# Adafruit_PCF8591.net
KiCad netlist of a schematic drawn in EAGLE
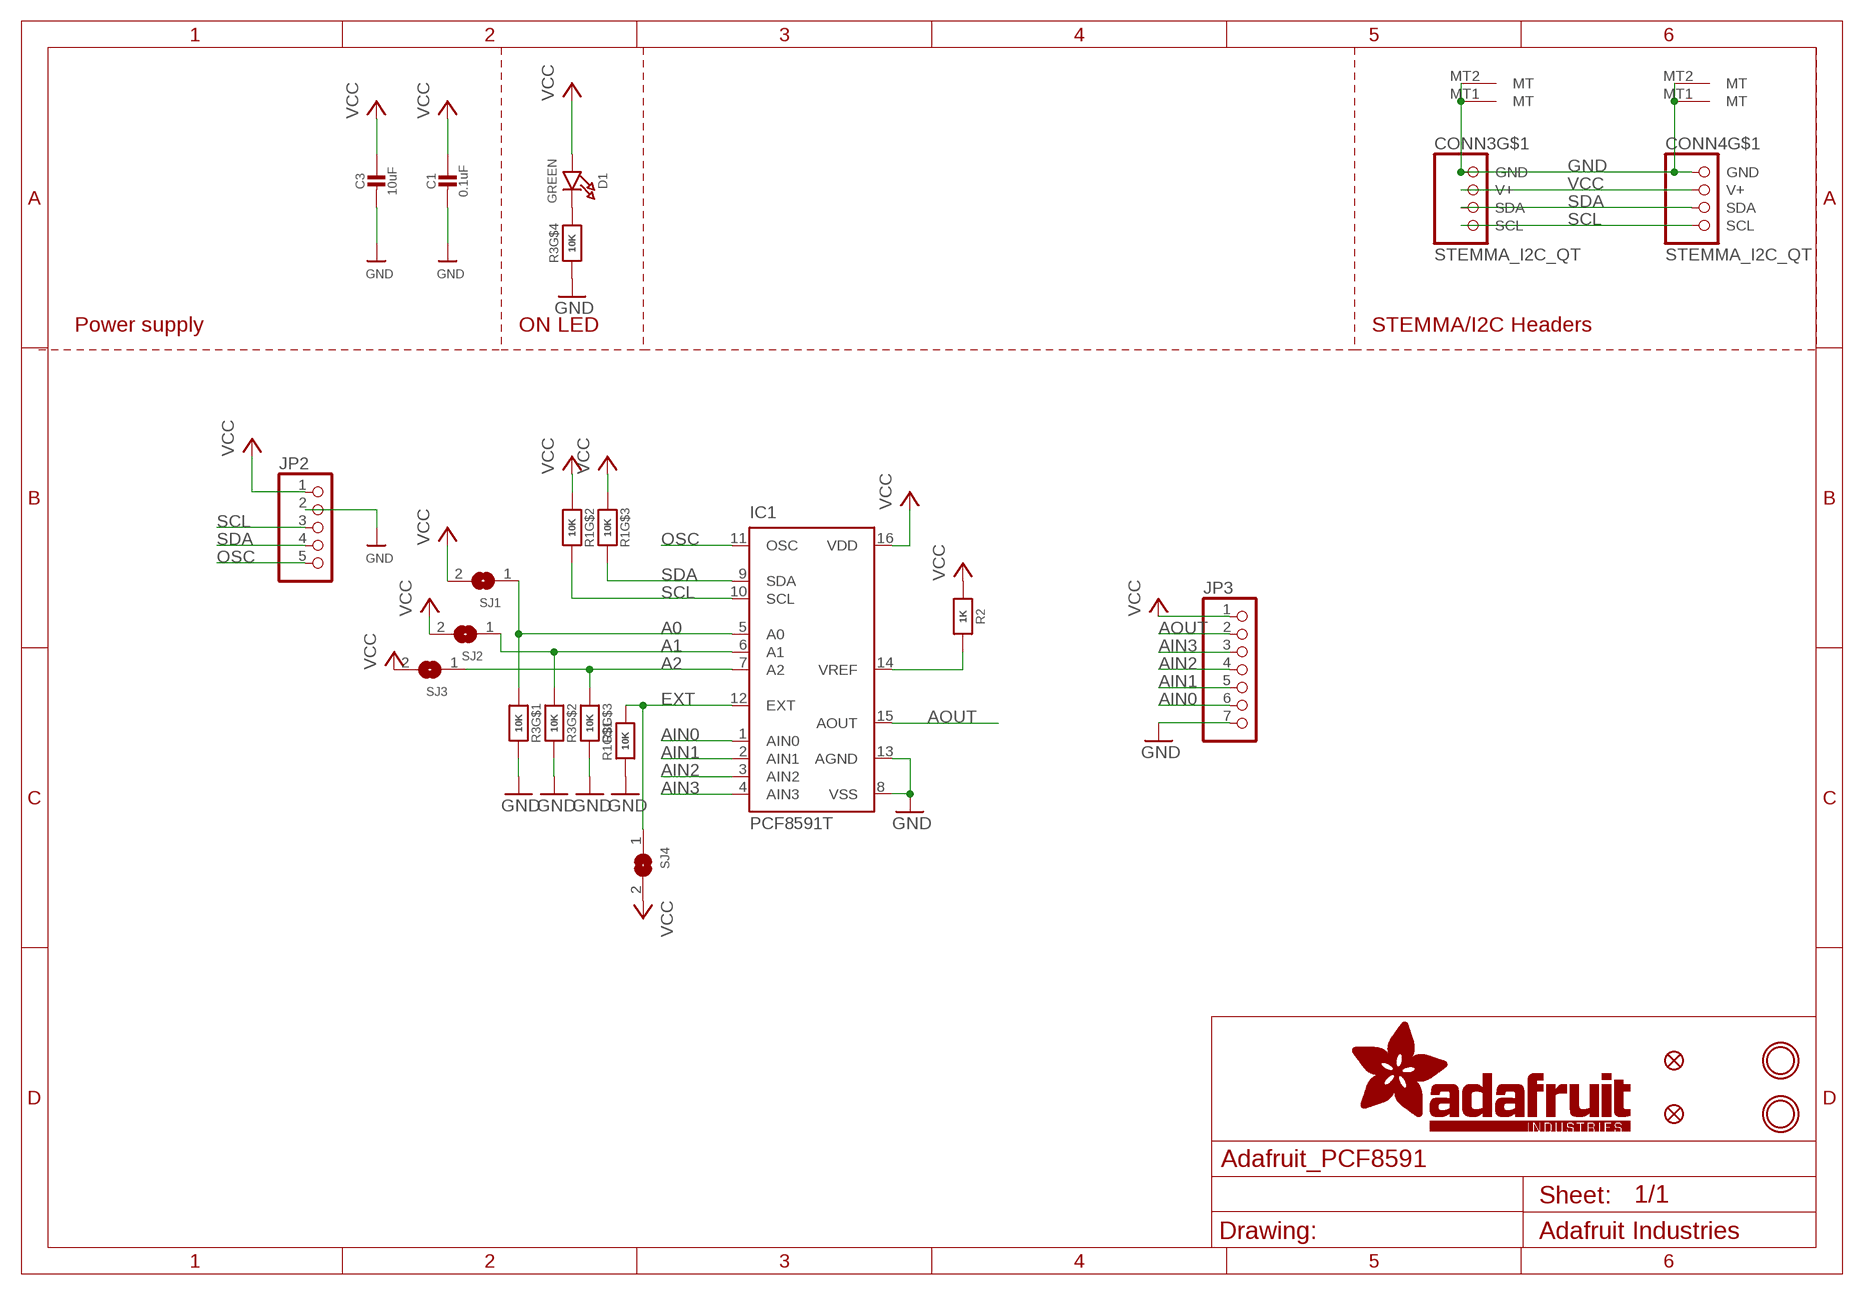
[diagram p0: schematic, sheet 1]

(export (version "E")
  (design (tool "Eeschema 10.0.6"))
  (components
    (comp (ref "C1")
      (value "0.1uF")
      (footprint "eagle-import:0603-NO")
      (libsource (lib "eagle-import") (part "CAP_CERAMIC0603_NO"))
    )
    (comp (ref "C3")
      (value "10uF")
      (footprint "eagle-import:0805-NO")
      (libsource (lib "eagle-import") (part "CAP_CERAMIC0805-NOOUTLINE"))
    )
    (comp (ref "CONN3")
      (value "STEMMA_I2C_QT")
      (footprint "eagle-import:JST_SH4")
      (libsource (lib "eagle-import") (part "STEMMA_I2C_QT"))
    )
    (comp (ref "CONN4")
      (value "STEMMA_I2C_QT")
      (footprint "eagle-import:JST_SH4")
      (libsource (lib "eagle-import") (part "STEMMA_I2C_QT"))
    )
    (comp (ref "D1")
      (value "GREEN")
      (footprint "eagle-import:CHIPLED_0603_NOOUTLINE")
      (libsource (lib "eagle-import") (part "LED0603_NOOUTLINE"))
    )
    (comp (ref "FID3")
      (value "FIDUCIAL_1MM")
      (footprint "eagle-import:FIDUCIAL_1MM")
      (libsource (lib "eagle-import") (part "FIDUCIAL_1MM"))
    )
    (comp (ref "FID4")
      (value "FIDUCIAL_1MM")
      (footprint "eagle-import:FIDUCIAL_1MM")
      (libsource (lib "eagle-import") (part "FIDUCIAL_1MM"))
    )
    (comp (ref "IC1")
      (value "PCF8591T")
      (footprint "eagle-import:SO16W")
      (fields (field (name "MPN") "PCF8591T/2,512"))
      (libsource (lib "eagle-import") (part "PCF8591T"))
    )
    (comp (ref "JP2")
      (value "HEADER-1X570MIL")
      (footprint "eagle-import:1X05_ROUND_70")
      (libsource (lib "eagle-import") (part "HEADER-1X570MIL"))
    )
    (comp (ref "JP3")
      (value "HEADER-1X770MIL")
      (footprint "eagle-import:1X07_ROUND_70")
      (libsource (lib "eagle-import") (part "HEADER-1X770MIL"))
    )
    (comp (ref "R1")
      (value "10K")
      (footprint "eagle-import:RESPACK_4X0603")
      (libsource (lib "eagle-import") (part "RESISTOR_4PACK"))
    )
    (comp (ref "R2")
      (value "1K")
      (footprint "eagle-import:0603-NO")
      (libsource (lib "eagle-import") (part "RESISTOR_0603_NOOUT"))
    )
    (comp (ref "R3")
      (value "10K")
      (footprint "eagle-import:RESPACK_4X0603")
      (libsource (lib "eagle-import") (part "RESISTOR_4PACK"))
    )
    (comp (ref "SJ1")
      (value "SOLDERJUMPER")
      (footprint "eagle-import:SOLDERJUMPER_ARROW_NOPASTE")
      (libsource (lib "eagle-import") (part "SOLDERJUMPER"))
    )
    (comp (ref "SJ2")
      (value "SOLDERJUMPER")
      (footprint "eagle-import:SOLDERJUMPER_ARROW_NOPASTE")
      (libsource (lib "eagle-import") (part "SOLDERJUMPER"))
    )
    (comp (ref "SJ3")
      (value "SOLDERJUMPER")
      (footprint "eagle-import:SOLDERJUMPER_ARROW_NOPASTE")
      (libsource (lib "eagle-import") (part "SOLDERJUMPER"))
    )
    (comp (ref "SJ4")
      (value "SOLDERJUMPER")
      (footprint "eagle-import:SOLDERJUMPER_ARROW_NOPASTE")
      (libsource (lib "eagle-import") (part "SOLDERJUMPER"))
    )
    (comp (ref "U$19")
      (value "MOUNTINGHOLE2.5")
      (footprint "eagle-import:MOUNTINGHOLE_2.5_PLATED")
      (libsource (lib "eagle-import") (part "MOUNTINGHOLE2.5"))
    )
    (comp (ref "U$21")
      (value "MOUNTINGHOLE2.5")
      (footprint "eagle-import:MOUNTINGHOLE_2.5_PLATED")
      (libsource (lib "eagle-import") (part "MOUNTINGHOLE2.5"))
    )
  )
  (nets
    (net (code "1") (name "/A0") (class "Default")
      (node (ref "IC1") (pin "5") (pinfunction "A0_5") (pintype "input"))
      (node (ref "R3") (pin "1") (pinfunction "1_1") (pintype "passive"))
      (node (ref "SJ1") (pin "1") (pinfunction "1_1") (pintype "passive"))
    )
    (net (code "2") (name "/A1") (class "Default")
      (node (ref "IC1") (pin "6") (pinfunction "A1_6") (pintype "input"))
      (node (ref "R3") (pin "2") (pinfunction "1_2") (pintype "passive"))
      (node (ref "SJ2") (pin "1") (pinfunction "1_1") (pintype "passive"))
    )
    (net (code "3") (name "/A2") (class "Default")
      (node (ref "IC1") (pin "7") (pinfunction "A2_7") (pintype "input"))
      (node (ref "R3") (pin "3") (pinfunction "1_3") (pintype "passive"))
      (node (ref "SJ3") (pin "1") (pinfunction "1_1") (pintype "passive"))
    )
    (net (code "4") (name "/AIN0") (class "Default")
      (node (ref "IC1") (pin "1") (pinfunction "AIN0_1") (pintype "input"))
      (node (ref "JP3") (pin "6") (pinfunction "6_6") (pintype "passive"))
    )
    (net (code "5") (name "/AIN1") (class "Default")
      (node (ref "IC1") (pin "2") (pinfunction "AIN1_2") (pintype "input"))
      (node (ref "JP3") (pin "5") (pinfunction "5_5") (pintype "passive"))
    )
    (net (code "6") (name "/AIN2") (class "Default")
      (node (ref "IC1") (pin "3") (pinfunction "AIN2_3") (pintype "input"))
      (node (ref "JP3") (pin "4") (pinfunction "4_4") (pintype "passive"))
    )
    (net (code "7") (name "/AIN3") (class "Default")
      (node (ref "IC1") (pin "4") (pinfunction "AIN3_4") (pintype "input"))
      (node (ref "JP3") (pin "3") (pinfunction "3_3") (pintype "passive"))
    )
    (net (code "8") (name "/AOUT") (class "Default")
      (node (ref "IC1") (pin "15") (pinfunction "AOUT_15") (pintype "output"))
      (node (ref "JP3") (pin "2") (pinfunction "2_2") (pintype "passive"))
    )
    (net (code "9") (name "/EXT") (class "Default")
      (node (ref "IC1") (pin "12") (pinfunction "EXT_12") (pintype "input"))
      (node (ref "R1") (pin "8") (pinfunction "2_8") (pintype "passive"))
      (node (ref "SJ4") (pin "1") (pinfunction "1_1") (pintype "passive"))
    )
    (net (code "10") (name "/OSC") (class "Default")
      (node (ref "IC1") (pin "11") (pinfunction "OSC_11") (pintype "input"))
      (node (ref "JP2") (pin "5") (pinfunction "5_5") (pintype "passive"))
    )
    (net (code "11") (name "/SCL") (class "Default")
      (node (ref "CONN3") (pin "4") (pinfunction "SCL_4") (pintype "passive"))
      (node (ref "CONN4") (pin "4") (pinfunction "SCL_4") (pintype "passive"))
      (node (ref "IC1") (pin "10") (pinfunction "SCL_10") (pintype "input"))
      (node (ref "JP2") (pin "3") (pinfunction "3_3") (pintype "passive"))
      (node (ref "R1") (pin "7") (pinfunction "2_7") (pintype "passive"))
    )
    (net (code "12") (name "/SDA") (class "Default")
      (node (ref "CONN3") (pin "3") (pinfunction "SDA_3") (pintype "passive"))
      (node (ref "CONN4") (pin "3") (pinfunction "SDA_3") (pintype "passive"))
      (node (ref "IC1") (pin "9") (pinfunction "SDA_9") (pintype "bidirectional"))
      (node (ref "JP2") (pin "4") (pinfunction "4_4") (pintype "passive"))
      (node (ref "R1") (pin "6") (pinfunction "2_6") (pintype "passive"))
    )
    (net (code "13") (name "GND") (class "Default")
      (node (ref "C1") (pin "2") (pinfunction "2_2") (pintype "passive"))
      (node (ref "C3") (pin "2") (pinfunction "2_2") (pintype "passive"))
      (node (ref "CONN3") (pin "1") (pinfunction "GND_1") (pintype "passive"))
      (node (ref "CONN3") (pin "MT1") (pinfunction "MT_MT1") (pintype "bidirectional"))
      (node (ref "CONN3") (pin "MT2") (pinfunction "MT_MT2") (pintype "bidirectional"))
      (node (ref "CONN4") (pin "1") (pinfunction "GND_1") (pintype "passive"))
      (node (ref "CONN4") (pin "MT1") (pinfunction "MT_MT1") (pintype "bidirectional"))
      (node (ref "CONN4") (pin "MT2") (pinfunction "MT_MT2") (pintype "bidirectional"))
      (node (ref "IC1") (pin "13") (pinfunction "AGND_13") (pintype "power_in"))
      (node (ref "IC1") (pin "8") (pinfunction "VSS_8") (pintype "power_in"))
      (node (ref "JP2") (pin "2") (pinfunction "2_2") (pintype "passive"))
      (node (ref "JP3") (pin "7") (pinfunction "7_7") (pintype "passive"))
      (node (ref "R1") (pin "1") (pinfunction "1_1") (pintype "passive"))
      (node (ref "R3") (pin "4") (pinfunction "1_4") (pintype "passive"))
      (node (ref "R3") (pin "6") (pinfunction "2_6") (pintype "passive"))
      (node (ref "R3") (pin "7") (pinfunction "2_7") (pintype "passive"))
      (node (ref "R3") (pin "8") (pinfunction "2_8") (pintype "passive"))
    )
    (net (code "14") (name "Net-(IC1-VREF)") (class "Default")
      (node (ref "IC1") (pin "14") (pinfunction "VREF_14") (pintype "input"))
      (node (ref "R2") (pin "2") (pinfunction "2_2") (pintype "passive"))
    )
    (net (code "15") (name "Net-(R3D-2)") (class "Default")
      (node (ref "D1") (pin "C") (pinfunction "C_C") (pintype "passive"))
      (node (ref "R3") (pin "5") (pinfunction "2_5") (pintype "passive"))
    )
    (net (code "16") (name "VCC") (class "Default")
      (node (ref "C1") (pin "1") (pinfunction "1_1") (pintype "passive"))
      (node (ref "C3") (pin "1") (pinfunction "1_1") (pintype "passive"))
      (node (ref "CONN3") (pin "2") (pinfunction "V+_2") (pintype "passive"))
      (node (ref "CONN4") (pin "2") (pinfunction "V+_2") (pintype "passive"))
      (node (ref "D1") (pin "A") (pinfunction "A_A") (pintype "passive"))
      (node (ref "IC1") (pin "16") (pinfunction "VDD_16") (pintype "power_in"))
      (node (ref "JP2") (pin "1") (pinfunction "1_1") (pintype "passive"))
      (node (ref "JP3") (pin "1") (pinfunction "1_1") (pintype "passive"))
      (node (ref "R1") (pin "2") (pinfunction "1_2") (pintype "passive"))
      (node (ref "R1") (pin "3") (pinfunction "1_3") (pintype "passive"))
      (node (ref "R2") (pin "1") (pinfunction "1_1") (pintype "passive"))
      (node (ref "SJ1") (pin "2") (pinfunction "2_2") (pintype "passive"))
      (node (ref "SJ2") (pin "2") (pinfunction "2_2") (pintype "passive"))
      (node (ref "SJ3") (pin "2") (pinfunction "2_2") (pintype "passive"))
      (node (ref "SJ4") (pin "2") (pinfunction "2_2") (pintype "passive"))
    )
  )
)
